# 02_V5_IO1.net
KiCad netlist of a schematic drawn in Altium Designer
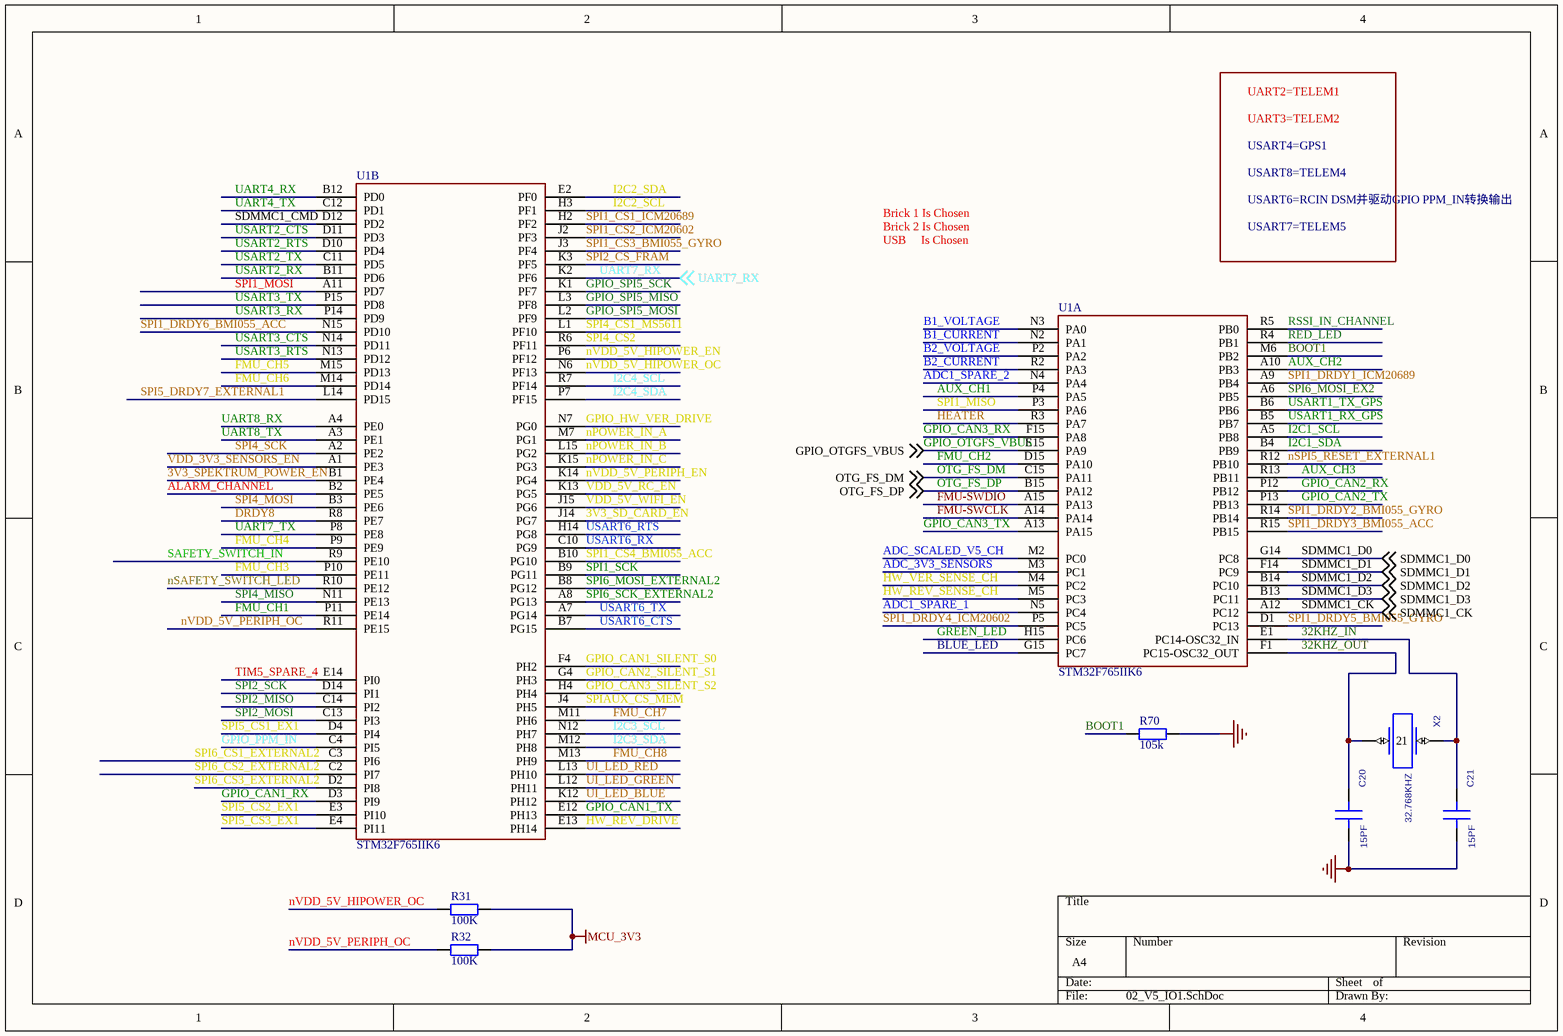
[diagram p0: 02_V5_IO1.SchDoc]

(export (version "E")
  (design (tool "Eeschema 10.0.6"))
  (components
    (comp (ref "C20") (value "15PF") (footprint "SC0402") (libsource (lib "*") (part "C")))
    (comp (ref "C21") (value "15PF") (footprint "SC0402") (libsource (lib "*") (part "C")))
    (comp (ref "R31")
      (value "100K")
      (description "Resistor")
      (fields (field (name "PUBLISHER") "Altium Limited"))
      (libsource (lib "Miscellaneous Devices") (part "Res2"))
    )
    (comp (ref "R32")
      (value "100K")
      (description "Resistor")
      (fields (field (name "PUBLISHER") "Altium Limited"))
      (libsource (lib "Miscellaneous Devices") (part "Res2"))
    )
    (comp (ref "R70")
      (value "105k")
      (description "Resistor")
      (fields (field (name "PUBLISHER") "Altium Limited"))
      (libsource (lib "Miscellaneous Devices") (part "Res2"))
    )
    (comp (ref "U1")
      (value "STM32F765IIK6")
      (footprint "UFBGA176")
      (libsource (lib "CUAV") (part "STM32F765IIK6"))
    )
    (comp (ref "X2") (value "32.768KHZ") (footprint "ABS06") (libsource (lib "*") (part "X_0")))
  )
  (nets
    (net (code "1") (name "/3V3_SD_CARD_EN") (class "Default")
      (node (ref "U1") (pin "J14") (pinfunction "PG7_J14") (pintype "passive"))
    )
    (net (code "2") (name "/3V3_SPEKTRUM_POWER_EN") (class "Default")
      (node (ref "U1") (pin "B1") (pinfunction "PE4_B1") (pintype "passive"))
    )
    (net (code "3") (name "/32KHZ_IN") (class "Default")
      (node (ref "C21") (pin "1") (pinfunction "A_1") (pintype "bidirectional"))
      (node (ref "U1") (pin "E1") (pinfunction "PC14-OSC32_IN_E1") (pintype "passive"))
      (node (ref "X2") (pin "1") (pinfunction "1_1") (pintype "bidirectional"))
    )
    (net (code "4") (name "/32KHZ_OUT") (class "Default")
      (node (ref "C20") (pin "1") (pinfunction "A_1") (pintype "bidirectional"))
      (node (ref "U1") (pin "F1") (pinfunction "PC15-OSC32_OUT_F1") (pintype "passive"))
      (node (ref "X2") (pin "2") (pinfunction "2_2") (pintype "bidirectional"))
    )
    (net (code "5") (name "/ADC1_SPARE_1") (class "Default")
      (node (ref "U1") (pin "N5") (pinfunction "PC4_N5") (pintype "passive"))
    )
    (net (code "6") (name "/ADC1_SPARE_2") (class "Default")
      (node (ref "U1") (pin "N4") (pinfunction "PA4_N4") (pintype "passive"))
    )
    (net (code "7") (name "/ADC_3V3_SENSORS") (class "Default")
      (node (ref "U1") (pin "M3") (pinfunction "PC1_M3") (pintype "passive"))
    )
    (net (code "8") (name "/ADC_SCALED_V5_CH") (class "Default")
      (node (ref "U1") (pin "M2") (pinfunction "PC0_M2") (pintype "passive"))
    )
    (net (code "9") (name "/ALARM_CHANNEL") (class "Default")
      (node (ref "U1") (pin "B2") (pinfunction "PE5_B2") (pintype "passive"))
    )
    (net (code "10") (name "/AUX_CH1") (class "Default")
      (node (ref "U1") (pin "P4") (pinfunction "PA5_P4") (pintype "passive"))
    )
    (net (code "11") (name "/AUX_CH2") (class "Default")
      (node (ref "U1") (pin "A10") (pinfunction "PB3_A10") (pintype "passive"))
    )
    (net (code "12") (name "/AUX_CH3") (class "Default")
      (node (ref "U1") (pin "R13") (pinfunction "PB11_R13") (pintype "passive"))
    )
    (net (code "13") (name "/B1_CURRENT") (class "Default")
      (node (ref "U1") (pin "N2") (pinfunction "PA1_N2") (pintype "passive"))
    )
    (net (code "14") (name "/B1_VOLTAGE") (class "Default")
      (node (ref "U1") (pin "N3") (pinfunction "PA0_N3") (pintype "passive"))
    )
    (net (code "15") (name "/B2_CURRENT") (class "Default")
      (node (ref "U1") (pin "R2") (pinfunction "PA3_R2") (pintype "passive"))
    )
    (net (code "16") (name "/B2_VOLTAGE") (class "Default")
      (node (ref "U1") (pin "P2") (pinfunction "PA2_P2") (pintype "passive"))
    )
    (net (code "17") (name "/BLUE_LED") (class "Default")
      (node (ref "U1") (pin "G15") (pinfunction "PC7_G15") (pintype "passive"))
    )
    (net (code "18") (name "/BOOT1") (class "Default")
      (node (ref "R70") (pin "1") (pinfunction "1_1") (pintype "passive"))
      (node (ref "U1") (pin "M6") (pinfunction "PB2_M6") (pintype "passive"))
    )
    (net (code "21") (name "/DRDY8") (class "Default")
      (node (ref "U1") (pin "R8") (pinfunction "PE7_R8") (pintype "passive"))
    )
    (net (code "22") (name "/FMU-SWCLK") (class "Default")
      (node (ref "U1") (pin "A14") (pinfunction "PA14_A14") (pintype "passive"))
    )
    (net (code "23") (name "/FMU-SWDIO") (class "Default")
      (node (ref "U1") (pin "A15") (pinfunction "PA13_A15") (pintype "passive"))
    )
    (net (code "24") (name "/FMU_CH1") (class "Default")
      (node (ref "U1") (pin "P11") (pinfunction "PE14_P11") (pintype "passive"))
    )
    (net (code "25") (name "/FMU_CH2") (class "Default")
      (node (ref "U1") (pin "D15") (pinfunction "PA10_D15") (pintype "passive"))
    )
    (net (code "26") (name "/FMU_CH3") (class "Default")
      (node (ref "U1") (pin "P10") (pinfunction "PE11_P10") (pintype "passive"))
    )
    (net (code "27") (name "/FMU_CH4") (class "Default")
      (node (ref "U1") (pin "P9") (pinfunction "PE9_P9") (pintype "passive"))
    )
    (net (code "28") (name "/FMU_CH5") (class "Default")
      (node (ref "U1") (pin "M15") (pinfunction "PD13_M15") (pintype "passive"))
    )
    (net (code "29") (name "/FMU_CH6") (class "Default")
      (node (ref "U1") (pin "M14") (pinfunction "PD14_M14") (pintype "passive"))
    )
    (net (code "30") (name "/FMU_CH7") (class "Default")
      (node (ref "U1") (pin "M11") (pinfunction "PH6_M11") (pintype "passive"))
    )
    (net (code "31") (name "/FMU_CH8") (class "Default")
      (node (ref "U1") (pin "M13") (pinfunction "PH9_M13") (pintype "passive"))
    )
    (net (code "32") (name "/GPIO_CAN1_RX") (class "Default")
      (node (ref "U1") (pin "D3") (pinfunction "PI9_D3") (pintype "passive"))
    )
    (net (code "33") (name "/GPIO_CAN1_SILENT_S0") (class "Default")
      (node (ref "U1") (pin "F4") (pinfunction "PH2_F4") (pintype "passive"))
    )
    (net (code "34") (name "/GPIO_CAN1_TX") (class "Default")
      (node (ref "U1") (pin "E12") (pinfunction "PH13_E12") (pintype "passive"))
    )
    (net (code "35") (name "/GPIO_CAN2_RX") (class "Default")
      (node (ref "U1") (pin "P12") (pinfunction "PB12_P12") (pintype "passive"))
    )
    (net (code "36") (name "/GPIO_CAN2_SILENT_S1") (class "Default")
      (node (ref "U1") (pin "G4") (pinfunction "PH3_G4") (pintype "passive"))
    )
    (net (code "37") (name "/GPIO_CAN2_TX") (class "Default")
      (node (ref "U1") (pin "P13") (pinfunction "PB13_P13") (pintype "passive"))
    )
    (net (code "38") (name "/GPIO_CAN3_RX") (class "Default")
      (node (ref "U1") (pin "F15") (pinfunction "PA8_F15") (pintype "passive"))
    )
    (net (code "39") (name "/GPIO_CAN3_SILENT_S2") (class "Default")
      (node (ref "U1") (pin "H4") (pinfunction "PH4_H4") (pintype "passive"))
    )
    (net (code "40") (name "/GPIO_CAN3_TX") (class "Default")
      (node (ref "U1") (pin "A13") (pinfunction "PA15_A13") (pintype "passive"))
    )
    (net (code "41") (name "/GPIO_HW_VER_DRIVE") (class "Default")
      (node (ref "U1") (pin "N7") (pinfunction "PG0_N7") (pintype "passive"))
    )
    (net (code "42") (name "/GPIO_PPM_IN") (class "Default")
      (node (ref "U1") (pin "C4") (pinfunction "PI5_C4") (pintype "passive"))
    )
    (net (code "43") (name "/GPIO_SPI5_MISO") (class "Default")
      (node (ref "U1") (pin "L3") (pinfunction "PF8_L3") (pintype "passive"))
    )
    (net (code "44") (name "/GPIO_SPI5_MOSI") (class "Default")
      (node (ref "U1") (pin "L2") (pinfunction "PF9_L2") (pintype "passive"))
    )
    (net (code "45") (name "/GPIO_SPI5_SCK") (class "Default")
      (node (ref "U1") (pin "K1") (pinfunction "PF7_K1") (pintype "passive"))
    )
    (net (code "46") (name "/GREEN_LED") (class "Default")
      (node (ref "U1") (pin "H15") (pinfunction "PC6_H15") (pintype "passive"))
    )
    (net (code "47") (name "/HEATER") (class "Default")
      (node (ref "U1") (pin "R3") (pinfunction "PA7_R3") (pintype "passive"))
    )
    (net (code "48") (name "/HW_REV_DRIVE") (class "Default")
      (node (ref "U1") (pin "E13") (pinfunction "PH14_E13") (pintype "passive"))
    )
    (net (code "49") (name "/HW_REV_SENSE_CH") (class "Default")
      (node (ref "U1") (pin "M5") (pinfunction "PC3_M5") (pintype "passive"))
    )
    (net (code "50") (name "/HW_VER_SENSE_CH") (class "Default")
      (node (ref "U1") (pin "M4") (pinfunction "PC2_M4") (pintype "passive"))
    )
    (net (code "51") (name "/I2C1_SCL") (class "Default")
      (node (ref "U1") (pin "A5") (pinfunction "PB8_A5") (pintype "passive"))
    )
    (net (code "52") (name "/I2C1_SDA") (class "Default")
      (node (ref "U1") (pin "B4") (pinfunction "PB9_B4") (pintype "passive"))
    )
    (net (code "53") (name "/I2C2_SCL") (class "Default")
      (node (ref "U1") (pin "H3") (pinfunction "PF1_H3") (pintype "passive"))
    )
    (net (code "54") (name "/I2C2_SDA") (class "Default")
      (node (ref "U1") (pin "E2") (pinfunction "PF0_E2") (pintype "passive"))
    )
    (net (code "55") (name "/I2C3_SCL") (class "Default")
      (node (ref "U1") (pin "N12") (pinfunction "PH7_N12") (pintype "passive"))
    )
    (net (code "56") (name "/I2C3_SDA") (class "Default")
      (node (ref "U1") (pin "M12") (pinfunction "PH8_M12") (pintype "passive"))
    )
    (net (code "57") (name "/I2C4_SCL") (class "Default")
      (node (ref "U1") (pin "R7") (pinfunction "PF14_R7") (pintype "passive"))
    )
    (net (code "58") (name "/I2C4_SDA") (class "Default")
      (node (ref "U1") (pin "P7") (pinfunction "PF15_P7") (pintype "passive"))
    )
    (net (code "59") (name "/RED_LED") (class "Default")
      (node (ref "U1") (pin "R4") (pinfunction "PB1_R4") (pintype "passive"))
    )
    (net (code "60") (name "/RSSI_IN_CHANNEL") (class "Default")
      (node (ref "U1") (pin "R5") (pinfunction "PB0_R5") (pintype "passive"))
    )
    (net (code "61") (name "/SAFETY_SWITCH_IN") (class "Default")
      (node (ref "U1") (pin "R9") (pinfunction "PE10_R9") (pintype "passive"))
    )
    (net (code "62") (name "/SDMMC1_CMD") (class "Default")
      (node (ref "U1") (pin "D12") (pinfunction "PD2_D12") (pintype "passive"))
    )
    (net (code "63") (name "/SPI1_CS1_ICM20689") (class "Default")
      (node (ref "U1") (pin "H2") (pinfunction "PF2_H2") (pintype "passive"))
    )
    (net (code "64") (name "/SPI1_CS2_ICM20602") (class "Default")
      (node (ref "U1") (pin "J2") (pinfunction "PF3_J2") (pintype "passive"))
    )
    (net (code "65") (name "/SPI1_CS3_BMI055_GYRO") (class "Default")
      (node (ref "U1") (pin "J3") (pinfunction "PF4_J3") (pintype "passive"))
    )
    (net (code "66") (name "/SPI1_CS4_BMI055_ACC") (class "Default")
      (node (ref "U1") (pin "B10") (pinfunction "PG10_B10") (pintype "passive"))
    )
    (net (code "67") (name "/SPI1_DRDY1_ICM20689") (class "Default")
      (node (ref "U1") (pin "A9") (pinfunction "PB4_A9") (pintype "passive"))
    )
    (net (code "68") (name "/SPI1_DRDY2_BMI055_GYRO") (class "Default")
      (node (ref "U1") (pin "R14") (pinfunction "PB14_R14") (pintype "passive"))
    )
    (net (code "69") (name "/SPI1_DRDY3_BMI055_ACC") (class "Default")
      (node (ref "U1") (pin "R15") (pinfunction "PB15_R15") (pintype "passive"))
    )
    (net (code "70") (name "/SPI1_DRDY4_ICM20602") (class "Default")
      (node (ref "U1") (pin "P5") (pinfunction "PC5_P5") (pintype "passive"))
    )
    (net (code "71") (name "/SPI1_DRDY5_BMI055_GYRO") (class "Default")
      (node (ref "U1") (pin "D1") (pinfunction "PC13_D1") (pintype "passive"))
    )
    (net (code "72") (name "/SPI1_DRDY6_BMI055_ACC") (class "Default")
      (node (ref "U1") (pin "N15") (pinfunction "PD10_N15") (pintype "passive"))
    )
    (net (code "73") (name "/SPI1_MISO") (class "Default")
      (node (ref "U1") (pin "P3") (pinfunction "PA6_P3") (pintype "passive"))
    )
    (net (code "74") (name "/SPI1_MOSI") (class "Default")
      (node (ref "U1") (pin "A11") (pinfunction "PD7_A11") (pintype "passive"))
    )
    (net (code "75") (name "/SPI1_SCK") (class "Default")
      (node (ref "U1") (pin "B9") (pinfunction "PG11_B9") (pintype "passive"))
    )
    (net (code "76") (name "/SPI2_CS_FRAM") (class "Default")
      (node (ref "U1") (pin "K3") (pinfunction "PF5_K3") (pintype "passive"))
    )
    (net (code "77") (name "/SPI2_MISO") (class "Default")
      (node (ref "U1") (pin "C14") (pinfunction "PI2_C14") (pintype "passive"))
    )
    (net (code "78") (name "/SPI2_MOSI") (class "Default")
      (node (ref "U1") (pin "C13") (pinfunction "PI3_C13") (pintype "passive"))
    )
    (net (code "79") (name "/SPI2_SCK") (class "Default")
      (node (ref "U1") (pin "D14") (pinfunction "PI1_D14") (pintype "passive"))
    )
    (net (code "80") (name "/SPI4_CS1_MS5611") (class "Default")
      (node (ref "U1") (pin "L1") (pinfunction "PF10_L1") (pintype "passive"))
    )
    (net (code "81") (name "/SPI4_CS2") (class "Default")
      (node (ref "U1") (pin "R6") (pinfunction "PF11_R6") (pintype "passive"))
    )
    (net (code "82") (name "/SPI4_MISO") (class "Default")
      (node (ref "U1") (pin "N11") (pinfunction "PE13_N11") (pintype "passive"))
    )
    (net (code "83") (name "/SPI4_MOSI") (class "Default")
      (node (ref "U1") (pin "B3") (pinfunction "PE6_B3") (pintype "passive"))
    )
    (net (code "84") (name "/SPI4_SCK") (class "Default")
      (node (ref "U1") (pin "A2") (pinfunction "PE2_A2") (pintype "passive"))
    )
    (net (code "85") (name "/SPI5_CS1_EX1") (class "Default")
      (node (ref "U1") (pin "D4") (pinfunction "PI4_D4") (pintype "passive"))
    )
    (net (code "86") (name "/SPI5_CS2_EX1") (class "Default")
      (node (ref "U1") (pin "E3") (pinfunction "PI10_E3") (pintype "passive"))
    )
    (net (code "87") (name "/SPI5_CS3_EX1") (class "Default")
      (node (ref "U1") (pin "E4") (pinfunction "PI11_E4") (pintype "passive"))
    )
    (net (code "88") (name "/SPI5_DRDY7_EXTERNAL1") (class "Default")
      (node (ref "U1") (pin "L14") (pinfunction "PD15_L14") (pintype "passive"))
    )
    (net (code "89") (name "/SPI6_CS1_EXTERNAL2") (class "Default")
      (node (ref "U1") (pin "C3") (pinfunction "PI6_C3") (pintype "passive"))
    )
    (net (code "90") (name "/SPI6_CS2_EXTERNAL2") (class "Default")
      (node (ref "U1") (pin "C2") (pinfunction "PI7_C2") (pintype "passive"))
    )
    (net (code "91") (name "/SPI6_CS3_EXTERNAL2") (class "Default")
      (node (ref "U1") (pin "D2") (pinfunction "PI8_D2") (pintype "passive"))
    )
    (net (code "92") (name "/SPI6_MOSI_EX2") (class "Default")
      (node (ref "U1") (pin "A6") (pinfunction "PB5_A6") (pintype "passive"))
    )
    (net (code "93") (name "/SPI6_MOSI_EXTERNAL2") (class "Default")
      (node (ref "U1") (pin "B8") (pinfunction "PG12_B8") (pintype "passive"))
    )
    (net (code "94") (name "/SPI6_SCK_EXTERNAL2") (class "Default")
      (node (ref "U1") (pin "A8") (pinfunction "PG13_A8") (pintype "passive"))
    )
    (net (code "95") (name "/SPIAUX_CS_MEM") (class "Default")
      (node (ref "U1") (pin "J4") (pinfunction "PH5_J4") (pintype "passive"))
    )
    (net (code "96") (name "/TIM5_SPARE_4") (class "Default")
      (node (ref "U1") (pin "E14") (pinfunction "PI0_E14") (pintype "passive"))
    )
    (net (code "99") (name "/UART4_RX") (class "Default")
      (node (ref "U1") (pin "B12") (pinfunction "PD0_B12") (pintype "passive"))
    )
    (net (code "100") (name "/UART4_TX") (class "Default")
      (node (ref "U1") (pin "C12") (pinfunction "PD1_C12") (pintype "passive"))
    )
    (net (code "101") (name "/UART7_TX") (class "Default")
      (node (ref "U1") (pin "P8") (pinfunction "PE8_P8") (pintype "passive"))
    )
    (net (code "102") (name "/UART8_RX") (class "Default")
      (node (ref "U1") (pin "A4") (pinfunction "PE0_A4") (pintype "passive"))
    )
    (net (code "103") (name "/UART8_TX") (class "Default")
      (node (ref "U1") (pin "A3") (pinfunction "PE1_A3") (pintype "passive"))
    )
    (net (code "104") (name "/UI_LED_BLUE") (class "Default")
      (node (ref "U1") (pin "K12") (pinfunction "PH12_K12") (pintype "passive"))
    )
    (net (code "105") (name "/UI_LED_GREEN") (class "Default")
      (node (ref "U1") (pin "L12") (pinfunction "PH11_L12") (pintype "passive"))
    )
    (net (code "106") (name "/UI_LED_RED") (class "Default")
      (node (ref "U1") (pin "L13") (pinfunction "PH10_L13") (pintype "passive"))
    )
    (net (code "107") (name "/USART1_RX_GPS") (class "Default")
      (node (ref "U1") (pin "B5") (pinfunction "PB7_B5") (pintype "passive"))
    )
    (net (code "108") (name "/USART1_TX_GPS") (class "Default")
      (node (ref "U1") (pin "B6") (pinfunction "PB6_B6") (pintype "passive"))
    )
    (net (code "109") (name "/USART2_CTS") (class "Default")
      (node (ref "U1") (pin "D11") (pinfunction "PD3_D11") (pintype "passive"))
    )
    (net (code "110") (name "/USART2_RTS") (class "Default")
      (node (ref "U1") (pin "D10") (pinfunction "PD4_D10") (pintype "passive"))
    )
    (net (code "111") (name "/USART2_RX") (class "Default")
      (node (ref "U1") (pin "B11") (pinfunction "PD6_B11") (pintype "passive"))
    )
    (net (code "112") (name "/USART2_TX") (class "Default")
      (node (ref "U1") (pin "C11") (pinfunction "PD5_C11") (pintype "passive"))
    )
    (net (code "113") (name "/USART3_CTS") (class "Default")
      (node (ref "U1") (pin "N14") (pinfunction "PD11_N14") (pintype "passive"))
    )
    (net (code "114") (name "/USART3_RTS") (class "Default")
      (node (ref "U1") (pin "N13") (pinfunction "PD12_N13") (pintype "passive"))
    )
    (net (code "115") (name "/USART3_RX") (class "Default")
      (node (ref "U1") (pin "P14") (pinfunction "PD9_P14") (pintype "passive"))
    )
    (net (code "116") (name "/USART3_TX") (class "Default")
      (node (ref "U1") (pin "P15") (pinfunction "PD8_P15") (pintype "passive"))
    )
    (net (code "119") (name "/USART6_CTS") (class "Default")
      (node (ref "U1") (pin "B7") (pinfunction "PG15_B7") (pintype "passive"))
    )
    (net (code "120") (name "/USART6_RTS") (class "Default")
      (node (ref "U1") (pin "H14") (pinfunction "PG8_H14") (pintype "passive"))
    )
    (net (code "121") (name "/USART6_RX") (class "Default")
      (node (ref "U1") (pin "C10") (pinfunction "PG9_C10") (pintype "passive"))
    )
    (net (code "122") (name "/USART6_TX") (class "Default")
      (node (ref "U1") (pin "A7") (pinfunction "PG14_A7") (pintype "passive"))
    )
    (net (code "126") (name "/VDD_3V3_SENSORS_EN") (class "Default")
      (node (ref "U1") (pin "A1") (pinfunction "PE3_A1") (pintype "passive"))
    )
    (net (code "127") (name "/VDD_5V_RC_EN") (class "Default")
      (node (ref "U1") (pin "K13") (pinfunction "PG5_K13") (pintype "passive"))
    )
    (net (code "128") (name "/VDD_5V_WIFI_EN") (class "Default")
      (node (ref "U1") (pin "J15") (pinfunction "PG6_J15") (pintype "passive"))
    )
    (net (code "129") (name "/nPOWER_IN_A") (class "Default")
      (node (ref "U1") (pin "M7") (pinfunction "PG1_M7") (pintype "passive"))
    )
    (net (code "130") (name "/nPOWER_IN_B") (class "Default")
      (node (ref "U1") (pin "L15") (pinfunction "PG2_L15") (pintype "passive"))
    )
    (net (code "131") (name "/nPOWER_IN_C") (class "Default")
      (node (ref "U1") (pin "K15") (pinfunction "PG3_K15") (pintype "passive"))
    )
    (net (code "132") (name "/nSAFETY_SWITCH_LED") (class "Default")
      (node (ref "U1") (pin "R10") (pinfunction "PE12_R10") (pintype "passive"))
    )
    (net (code "133") (name "/nSPI5_RESET_EXTERNAL1") (class "Default")
      (node (ref "U1") (pin "R12") (pinfunction "PB10_R12") (pintype "passive"))
    )
    (net (code "134") (name "/nVDD_5V_HIPOWER_EN") (class "Default")
      (node (ref "U1") (pin "P6") (pinfunction "PF12_P6") (pintype "passive"))
    )
    (net (code "135") (name "/nVDD_5V_HIPOWER_OC") (class "Default")
      (node (ref "R31") (pin "1") (pinfunction "1_1") (pintype "passive"))
      (node (ref "U1") (pin "N6") (pinfunction "PF13_N6") (pintype "passive"))
    )
    (net (code "136") (name "/nVDD_5V_PERIPH_EN") (class "Default")
      (node (ref "U1") (pin "K14") (pinfunction "PG4_K14") (pintype "passive"))
    )
    (net (code "137") (name "/nVDD_5V_PERIPH_OC") (class "Default")
      (node (ref "R32") (pin "1") (pinfunction "1_1") (pintype "passive"))
      (node (ref "U1") (pin "R11") (pinfunction "PE15_R11") (pintype "passive"))
    )
    (net (code "138") (name "GND") (class "Default")
      (node (ref "C20") (pin "2") (pinfunction "B_2") (pintype "bidirectional"))
      (node (ref "C21") (pin "2") (pinfunction "B_2") (pintype "bidirectional"))
      (node (ref "R70") (pin "2") (pinfunction "2_2") (pintype "passive"))
    )
    (net (code "139") (name "GPIO_OTGFS_VBUS") (class "Default")
      (node (ref "U1") (pin "E15") (pinfunction "PA9_E15") (pintype "passive"))
    )
    (net (code "140") (name "MCU_3V3") (class "Default")
      (node (ref "R31") (pin "2") (pinfunction "2_2") (pintype "passive"))
      (node (ref "R32") (pin "2") (pinfunction "2_2") (pintype "passive"))
    )
    (net (code "141") (name "OTG_FS_DM") (class "Default")
      (node (ref "U1") (pin "C15") (pinfunction "PA11_C15") (pintype "passive"))
    )
    (net (code "142") (name "OTG_FS_DP") (class "Default")
      (node (ref "U1") (pin "B15") (pinfunction "PA12_B15") (pintype "passive"))
    )
    (net (code "143") (name "SDMMC1_CK") (class "Default")
      (node (ref "U1") (pin "A12") (pinfunction "PC12_A12") (pintype "passive"))
    )
    (net (code "144") (name "SDMMC1_D0") (class "Default")
      (node (ref "U1") (pin "G14") (pinfunction "PC8_G14") (pintype "passive"))
    )
    (net (code "145") (name "SDMMC1_D1") (class "Default")
      (node (ref "U1") (pin "F14") (pinfunction "PC9_F14") (pintype "passive"))
    )
    (net (code "146") (name "SDMMC1_D2") (class "Default")
      (node (ref "U1") (pin "B14") (pinfunction "PC10_B14") (pintype "passive"))
    )
    (net (code "147") (name "SDMMC1_D3") (class "Default")
      (node (ref "U1") (pin "B13") (pinfunction "PC11_B13") (pintype "passive"))
    )
    (net (code "148") (name "UART7_RX") (class "Default")
      (node (ref "U1") (pin "K2") (pinfunction "PF6_K2") (pintype "passive"))
    )
  )
)
